# UI_MAIN.net
KiCad netlist of a schematic drawn in Altium Designer
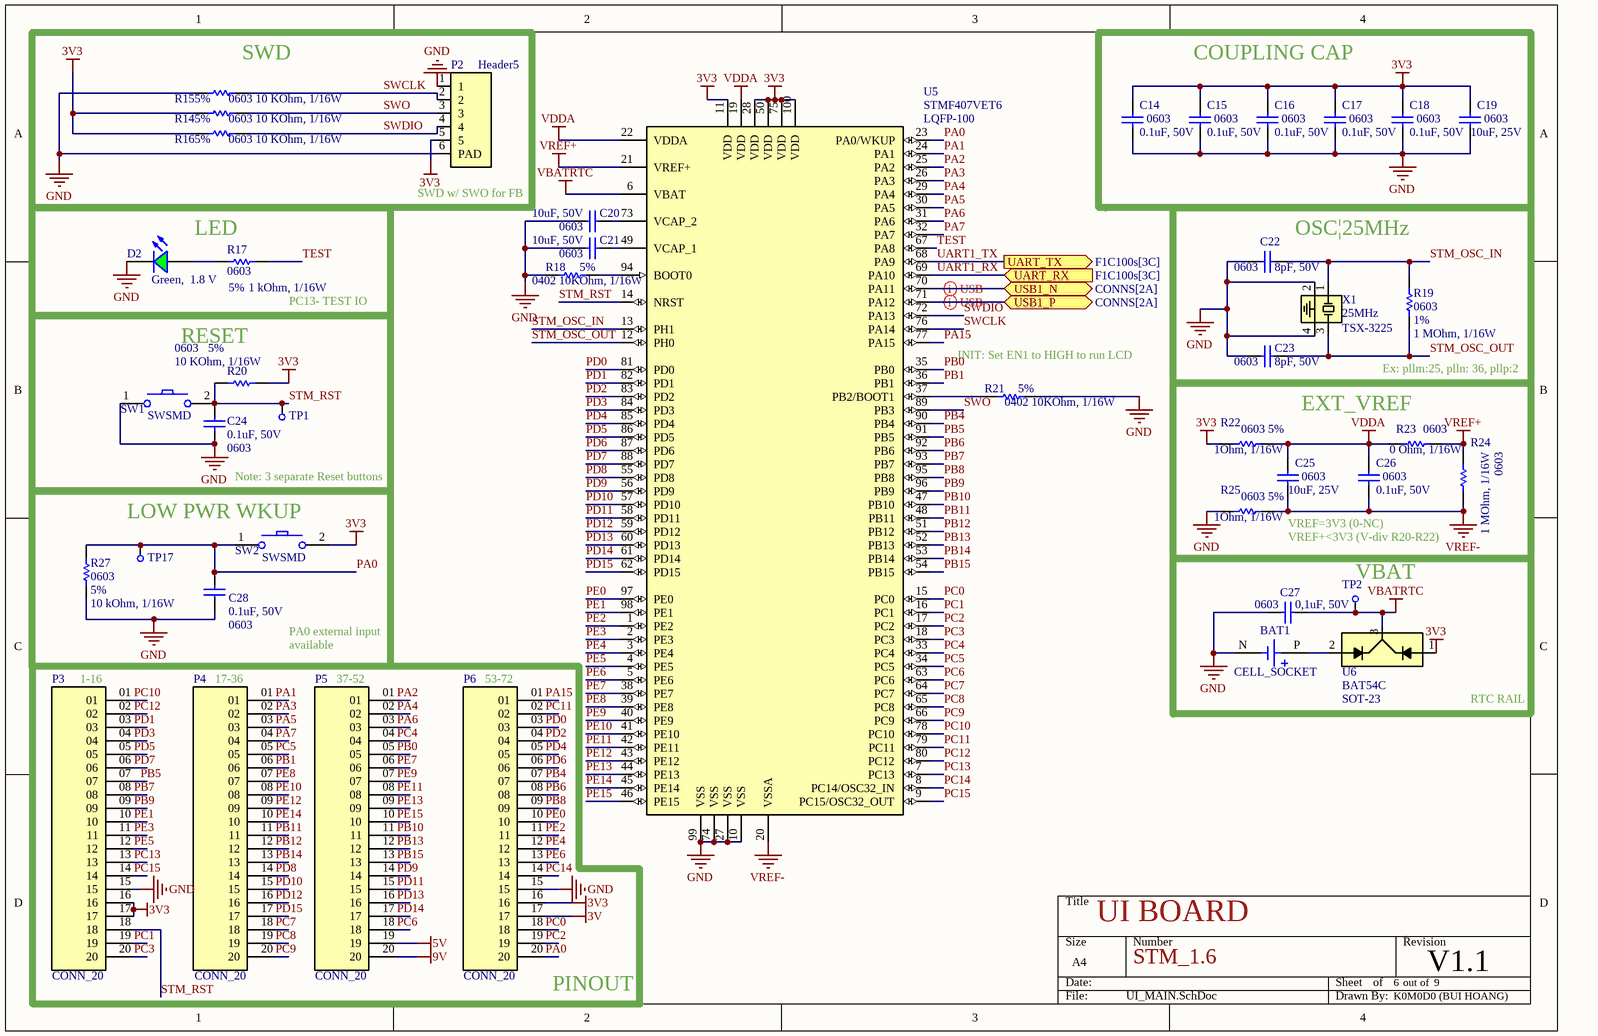
[diagram p0: UI_MAIN.SchDoc]

(export (version "E")
  (design (tool "Eeschema 10.0.6"))
  (components
    (comp (ref "BAT1")
      (value "CELL_SOCKET")
      (footprint "CELL_SOCKET")
      (description "Battery Holder (CELL_PIN)")
      (libsource (lib "DisplayLib") (part "CELL_SOCKET"))
    )
    (comp (ref "C14")
      (value "0.1uF, 50V")
      (footprint "C_0603")
      (description "CAP_0603")
      (fields (field (name "PACKAGE") "0603"))
      (libsource (lib "DisplayLib") (part "CAP_0603"))
    )
    (comp (ref "C15")
      (value "0.1uF, 50V")
      (footprint "C_0603")
      (description "CAP_0603")
      (fields (field (name "PACKAGE") "0603"))
      (libsource (lib "DisplayLib") (part "CAP_0603"))
    )
    (comp (ref "C16")
      (value "0.1uF, 50V")
      (footprint "C_0603")
      (description "CAP_0603")
      (fields (field (name "PACKAGE") "0603"))
      (libsource (lib "DisplayLib") (part "CAP_0603"))
    )
    (comp (ref "C17")
      (value "0.1uF, 50V")
      (footprint "C_0603")
      (description "CAP_0603")
      (fields (field (name "PACKAGE") "0603"))
      (libsource (lib "DisplayLib") (part "CAP_0603"))
    )
    (comp (ref "C18")
      (value "0.1uF, 50V")
      (footprint "C_0603")
      (description "CAP_0603")
      (fields (field (name "PACKAGE") "0603"))
      (libsource (lib "DisplayLib") (part "CAP_0603"))
    )
    (comp (ref "C19")
      (value "10uF, 25V")
      (footprint "C_0603")
      (description "CAP_0603")
      (fields (field (name "PACKAGE") "0603"))
      (libsource (lib "DisplayLib") (part "CAP_0603"))
    )
    (comp (ref "C20")
      (value "10uF, 50V")
      (footprint "C_0603")
      (description "CAP_0603")
      (fields (field (name "PACKAGE") "0603"))
      (libsource (lib "DisplayLib") (part "CAP_0603"))
    )
    (comp (ref "C21")
      (value "10uF, 50V")
      (footprint "C_0603")
      (description "CAP_0603")
      (fields (field (name "PACKAGE") "0603"))
      (libsource (lib "DisplayLib") (part "CAP_0603"))
    )
    (comp (ref "C22")
      (value "8pF, 50V")
      (footprint "C_0603")
      (description "CAP_0603")
      (fields (field (name "PACKAGE") "0603"))
      (libsource (lib "DisplayLib") (part "CAP_0603"))
    )
    (comp (ref "C23")
      (value "8pF, 50V")
      (footprint "C_0603")
      (description "CAP_0603")
      (fields (field (name "PACKAGE") "0603"))
      (libsource (lib "DisplayLib") (part "CAP_0603"))
    )
    (comp (ref "C24")
      (value "0.1uF, 50V")
      (footprint "C_0603")
      (description "CAP_0603")
      (fields (field (name "PACKAGE") "0603"))
      (libsource (lib "DisplayLib") (part "CAP_0603"))
    )
    (comp (ref "C25")
      (value "10uF, 25V")
      (footprint "C_0603")
      (description "CAP_0603")
      (fields (field (name "PACKAGE") "0603"))
      (libsource (lib "DisplayLib") (part "CAP_0603"))
    )
    (comp (ref "C26")
      (value "0.1uF, 50V")
      (footprint "C_0603")
      (description "CAP_0603")
      (fields (field (name "PACKAGE") "0603"))
      (libsource (lib "DisplayLib") (part "CAP_0603"))
    )
    (comp (ref "C27")
      (value "0,1uF, 50V")
      (footprint "C_0603")
      (description "CAP_0603")
      (fields (field (name "PACKAGE") "0603"))
      (libsource (lib "DisplayLib") (part "CAP_0603"))
    )
    (comp (ref "C28")
      (value "0.1uF, 50V")
      (footprint "C_0603")
      (description "CAP_0603")
      (fields (field (name "PACKAGE") "0603"))
      (libsource (lib "DisplayLib") (part "CAP_0603"))
    )
    (comp (ref "D2")
      (value "Green,  1.8 V")
      (footprint "LED_0603")
      (description "Green LED")
      (libsource (lib "DisplayLib") (part "GREEN"))
    )
    (comp (ref "P2")
      (value "Header5")
      (footprint "CONN_Header5")
      (description "Header 5 pins (2.54mm)")
      (libsource (lib "DisplayLib") (part "HEADER5"))
    )
    (comp (ref "P3")
      (value "CONN_20")
      (footprint "CONN_20")
      (description "Header 20 pins (2.54mm)")
      (libsource (lib "DisplayLib") (part "CONN_20"))
    )
    (comp (ref "P4")
      (value "CONN_20")
      (footprint "CONN_20")
      (description "Header 20 pins (2.54mm)")
      (libsource (lib "DisplayLib") (part "CONN_20"))
    )
    (comp (ref "P5")
      (value "CONN_20")
      (footprint "CONN_20")
      (description "Header 20 pins (2.54mm)")
      (libsource (lib "DisplayLib") (part "CONN_20"))
    )
    (comp (ref "P6")
      (value "CONN_20")
      (footprint "CONN_20")
      (description "Header 20 pins (2.54mm)")
      (libsource (lib "DisplayLib") (part "CONN_20"))
    )
    (comp (ref "R14")
      (value "10 KOhm, 1/16W")
      (footprint "R_0603")
      (description "RES_0603")
      (fields (field (name "PACKAGE") "0603") (field (name "ACC") "5%"))
      (libsource (lib "DisplayLib") (part "RES_0603"))
    )
    (comp (ref "R15")
      (value "10 KOhm, 1/16W")
      (footprint "R_0603")
      (description "RES_0603")
      (fields (field (name "PACKAGE") "0603") (field (name "ACC") "5%"))
      (libsource (lib "DisplayLib") (part "RES_0603"))
    )
    (comp (ref "R16")
      (value "10 KOhm, 1/16W")
      (footprint "R_0603")
      (description "RES_0603")
      (fields (field (name "PACKAGE") "0603") (field (name "ACC") "5%"))
      (libsource (lib "DisplayLib") (part "RES_0603"))
    )
    (comp (ref "R17")
      (value "1 kOhm, 1/16W")
      (footprint "R_0603")
      (description "RES_0603")
      (fields (field (name "PACKAGE") "0603") (field (name "ACC") "5%"))
      (libsource (lib "DisplayLib") (part "RES_0603"))
    )
    (comp (ref "R18")
      (value "10KOhm, 1/16W")
      (footprint "R_0402")
      (description "RES_0402")
      (fields (field (name "PACKAGE") "0402") (field (name "ACC") "5%"))
      (libsource (lib "DisplayLib") (part "RES_0402"))
    )
    (comp (ref "R19")
      (value "1 MOhm, 1/16W")
      (footprint "R_0603")
      (description "RES_0603")
      (fields (field (name "PACKAGE") "0603") (field (name "ACC") "1%"))
      (libsource (lib "DisplayLib") (part "RES_0603"))
    )
    (comp (ref "R20")
      (value "10 KOhm, 1/16W")
      (footprint "R_0603")
      (description "RES_0603")
      (fields (field (name "PACKAGE") "0603") (field (name "ACC") "5%"))
      (libsource (lib "DisplayLib") (part "RES_0603"))
    )
    (comp (ref "R21")
      (value "10KOhm, 1/16W")
      (footprint "R_0402")
      (description "RES_0402")
      (fields (field (name "PACKAGE") "0402") (field (name "ACC") "5%"))
      (libsource (lib "DisplayLib") (part "RES_0402"))
    )
    (comp (ref "R22")
      (value "1Ohm, 1/16W")
      (footprint "R_0603")
      (description "RES_0603")
      (fields (field (name "PACKAGE") "0603") (field (name "ACC") "5%"))
      (libsource (lib "DisplayLib") (part "RES_0603"))
    )
    (comp (ref "R23")
      (value "0 Ohm, 1/16W")
      (footprint "R_0603")
      (description "RES_0603")
      (fields (field (name "PACKAGE") "0603"))
      (libsource (lib "DisplayLib") (part "RES_0603"))
    )
    (comp (ref "R24")
      (value "1 MOhm, 1/16W")
      (footprint "R_0603")
      (description "RES_0603")
      (fields (field (name "PACKAGE") "0603"))
      (libsource (lib "DisplayLib") (part "RES_0603"))
    )
    (comp (ref "R25")
      (value "1Ohm, 1/16W")
      (footprint "R_0603")
      (description "RES_0603")
      (fields (field (name "PACKAGE") "0603") (field (name "ACC") "5%"))
      (libsource (lib "DisplayLib") (part "RES_0603"))
    )
    (comp (ref "R27")
      (value "10 kOhm, 1/16W")
      (footprint "R_0603")
      (description "RES_0603")
      (fields (field (name "PACKAGE") "0603") (field (name "ACC") "5%"))
      (libsource (lib "DisplayLib") (part "RES_0603"))
    )
    (comp (ref "SW1")
      (value "SWSMD")
      (footprint "SW_SMD_NOGND")
      (description "SW_SMD")
      (libsource (lib "DisplayLib") (part "SWSMD_NOGND"))
    )
    (comp (ref "SW2")
      (value "SWSMD")
      (footprint "SW_SMD_NOGND")
      (description "SW_SMD")
      (libsource (lib "DisplayLib") (part "SWSMD_NOGND"))
    )
    (comp (ref "TP1")
      (value "TESTPT")
      (footprint "TESTPT")
      (description "Test point")
      (libsource (lib "DisplayLib") (part "TESTPT"))
    )
    (comp (ref "TP2")
      (value "TESTPT")
      (footprint "TESTPT")
      (description "Test point")
      (libsource (lib "DisplayLib") (part "TESTPT"))
    )
    (comp (ref "TP17")
      (value "TESTPT")
      (footprint "TESTPT")
      (description "Test point")
      (libsource (lib "DisplayLib") (part "TESTPT"))
    )
    (comp (ref "U5")
      (value "STMF407VET6")
      (footprint "PKG_LQFP-100")
      (fields (field (name "PACKAGE") "LQFP-100"))
      (libsource (lib "DisplayLib") (part "STMF407VET6"))
    )
    (comp (ref "U6")
      (value "BAT54C")
      (footprint "PKG_SOT-23")
      (description "P-Channel 30 V 4A (Ta) 1.4W (Ta) Surface Mount SOT-23-3")
      (fields (field (name "PACKAGE") "SOT-23"))
      (libsource (lib "DisplayLib") (part "BAT54C"))
    )
    (comp (ref "X1")
      (value "25MHz")
      (footprint "PKG_TSX-3225")
      (description "Crystal, 25 MHz, -30 to 85 degC, 3.2 x 2.5 x 0.9 mm SMD")
      (fields (field (name "PACKAGE") "TSX-3225"))
      (libsource (lib "DisplayLib") (part "XTAL"))
    )
  )
  (nets
    (net (code "1") (name "/PA0") (class "Default")
      (node (ref "C28") (pin "2") (pinfunction "2_2") (pintype "passive"))
      (node (ref "P6") (pin "20") (pinfunction "20_20") (pintype "passive"))
      (node (ref "R27") (pin "2") (pinfunction "2_2") (pintype "passive"))
      (node (ref "SW2") (pin "1") (pinfunction "1_1") (pintype "passive"))
      (node (ref "TP17") (pin "1") (pinfunction "1_1") (pintype "passive"))
      (node (ref "U5") (pin "23") (pinfunction "PA0/WKUP_23") (pintype "bidirectional"))
    )
    (net (code "2") (name "/PA1") (class "Default")
      (node (ref "P4") (pin "01") (pinfunction "01_01") (pintype "passive"))
      (node (ref "U5") (pin "24") (pinfunction "PA1_24") (pintype "bidirectional"))
    )
    (net (code "3") (name "/PA2") (class "Default")
      (node (ref "P5") (pin "01") (pinfunction "01_01") (pintype "passive"))
      (node (ref "U5") (pin "25") (pinfunction "PA2_25") (pintype "bidirectional"))
    )
    (net (code "4") (name "/PA3") (class "Default")
      (node (ref "P4") (pin "02") (pinfunction "02_02") (pintype "passive"))
      (node (ref "U5") (pin "26") (pinfunction "PA3_26") (pintype "bidirectional"))
    )
    (net (code "5") (name "/PA4") (class "Default")
      (node (ref "P5") (pin "02") (pinfunction "02_02") (pintype "passive"))
      (node (ref "U5") (pin "29") (pinfunction "PA4_29") (pintype "bidirectional"))
    )
    (net (code "6") (name "/PA5") (class "Default")
      (node (ref "P4") (pin "03") (pinfunction "03_03") (pintype "passive"))
      (node (ref "U5") (pin "30") (pinfunction "PA5_30") (pintype "bidirectional"))
    )
    (net (code "7") (name "/PA6") (class "Default")
      (node (ref "P5") (pin "03") (pinfunction "03_03") (pintype "passive"))
      (node (ref "U5") (pin "31") (pinfunction "PA6_31") (pintype "bidirectional"))
    )
    (net (code "8") (name "/PA7") (class "Default")
      (node (ref "P4") (pin "04") (pinfunction "04_04") (pintype "passive"))
      (node (ref "U5") (pin "32") (pinfunction "PA7_32") (pintype "bidirectional"))
    )
    (net (code "9") (name "/PA15") (class "Default")
      (node (ref "P6") (pin "01") (pinfunction "01_01") (pintype "passive"))
      (node (ref "U5") (pin "77") (pinfunction "PA15_77") (pintype "bidirectional"))
    )
    (net (code "10") (name "/PB0") (class "Default")
      (node (ref "P5") (pin "05") (pinfunction "05_05") (pintype "passive"))
      (node (ref "U5") (pin "35") (pinfunction "PB0_35") (pintype "bidirectional"))
    )
    (net (code "11") (name "/PB1") (class "Default")
      (node (ref "P4") (pin "06") (pinfunction "06_06") (pintype "passive"))
      (node (ref "U5") (pin "36") (pinfunction "PB1_36") (pintype "bidirectional"))
    )
    (net (code "12") (name "/PB4") (class "Default")
      (node (ref "P6") (pin "07") (pinfunction "07_07") (pintype "passive"))
      (node (ref "U5") (pin "90") (pinfunction "PB4_90") (pintype "bidirectional"))
    )
    (net (code "13") (name "/PB5") (class "Default")
      (node (ref "P3") (pin "07") (pinfunction "07_07") (pintype "passive"))
      (node (ref "U5") (pin "91") (pinfunction "PB5_91") (pintype "bidirectional"))
    )
    (net (code "14") (name "/PB6") (class "Default")
      (node (ref "P6") (pin "08") (pinfunction "08_08") (pintype "passive"))
      (node (ref "U5") (pin "92") (pinfunction "PB6_92") (pintype "bidirectional"))
    )
    (net (code "15") (name "/PB7") (class "Default")
      (node (ref "P3") (pin "08") (pinfunction "08_08") (pintype "passive"))
      (node (ref "U5") (pin "93") (pinfunction "PB7_93") (pintype "bidirectional"))
    )
    (net (code "16") (name "/PB8") (class "Default")
      (node (ref "P6") (pin "09") (pinfunction "09_09") (pintype "passive"))
      (node (ref "U5") (pin "95") (pinfunction "PB8_95") (pintype "bidirectional"))
    )
    (net (code "17") (name "/PB9") (class "Default")
      (node (ref "P3") (pin "09") (pinfunction "09_09") (pintype "passive"))
      (node (ref "U5") (pin "96") (pinfunction "PB9_96") (pintype "bidirectional"))
    )
    (net (code "18") (name "/PB10") (class "Default")
      (node (ref "P5") (pin "11") (pinfunction "11_11") (pintype "passive"))
      (node (ref "U5") (pin "47") (pinfunction "PB10_47") (pintype "bidirectional"))
    )
    (net (code "19") (name "/PB11") (class "Default")
      (node (ref "P4") (pin "11") (pinfunction "11_11") (pintype "passive"))
      (node (ref "U5") (pin "48") (pinfunction "PB11_48") (pintype "bidirectional"))
    )
    (net (code "20") (name "/PB12") (class "Default")
      (node (ref "P4") (pin "12") (pinfunction "12_12") (pintype "passive"))
      (node (ref "U5") (pin "51") (pinfunction "PB12_51") (pintype "bidirectional"))
    )
    (net (code "21") (name "/PB13") (class "Default")
      (node (ref "P5") (pin "12") (pinfunction "12_12") (pintype "passive"))
      (node (ref "U5") (pin "52") (pinfunction "PB13_52") (pintype "bidirectional"))
    )
    (net (code "22") (name "/PB14") (class "Default")
      (node (ref "P4") (pin "13") (pinfunction "13_13") (pintype "passive"))
      (node (ref "U5") (pin "53") (pinfunction "PB14_53") (pintype "bidirectional"))
    )
    (net (code "23") (name "/PB15") (class "Default")
      (node (ref "P5") (pin "13") (pinfunction "13_13") (pintype "passive"))
      (node (ref "U5") (pin "54") (pinfunction "PB15_54") (pintype "bidirectional"))
    )
    (net (code "24") (name "/PC0") (class "Default")
      (node (ref "P6") (pin "18") (pinfunction "18_18") (pintype "passive"))
      (node (ref "U5") (pin "15") (pinfunction "PC0_15") (pintype "bidirectional"))
    )
    (net (code "25") (name "/PC1") (class "Default")
      (node (ref "P3") (pin "19") (pinfunction "19_19") (pintype "passive"))
      (node (ref "U5") (pin "16") (pinfunction "PC1_16") (pintype "bidirectional"))
    )
    (net (code "26") (name "/PC2") (class "Default")
      (node (ref "P6") (pin "19") (pinfunction "19_19") (pintype "passive"))
      (node (ref "U5") (pin "17") (pinfunction "PC2_17") (pintype "bidirectional"))
    )
    (net (code "27") (name "/PC3") (class "Default")
      (node (ref "P3") (pin "20") (pinfunction "20_20") (pintype "passive"))
      (node (ref "U5") (pin "18") (pinfunction "PC3_18") (pintype "bidirectional"))
    )
    (net (code "28") (name "/PC4") (class "Default")
      (node (ref "P5") (pin "04") (pinfunction "04_04") (pintype "passive"))
      (node (ref "U5") (pin "33") (pinfunction "PC4_33") (pintype "bidirectional"))
    )
    (net (code "29") (name "/PC5") (class "Default")
      (node (ref "P4") (pin "05") (pinfunction "05_05") (pintype "passive"))
      (node (ref "U5") (pin "34") (pinfunction "PC5_34") (pintype "bidirectional"))
    )
    (net (code "30") (name "/PC6") (class "Default")
      (node (ref "P5") (pin "18") (pinfunction "18_18") (pintype "passive"))
      (node (ref "U5") (pin "63") (pinfunction "PC6_63") (pintype "bidirectional"))
    )
    (net (code "31") (name "/PC7") (class "Default")
      (node (ref "P4") (pin "18") (pinfunction "18_18") (pintype "passive"))
      (node (ref "U5") (pin "64") (pinfunction "PC7_64") (pintype "bidirectional"))
    )
    (net (code "32") (name "/PC8") (class "Default")
      (node (ref "P4") (pin "19") (pinfunction "19_19") (pintype "passive"))
      (node (ref "U5") (pin "65") (pinfunction "PC8_65") (pintype "bidirectional"))
    )
    (net (code "33") (name "/PC9") (class "Default")
      (node (ref "P4") (pin "20") (pinfunction "20_20") (pintype "passive"))
      (node (ref "U5") (pin "66") (pinfunction "PC9_66") (pintype "bidirectional"))
    )
    (net (code "34") (name "/PC10") (class "Default")
      (node (ref "P3") (pin "01") (pinfunction "01_01") (pintype "passive"))
      (node (ref "U5") (pin "78") (pinfunction "PC10_78") (pintype "bidirectional"))
    )
    (net (code "35") (name "/PC11") (class "Default")
      (node (ref "P6") (pin "02") (pinfunction "02_02") (pintype "passive"))
      (node (ref "U5") (pin "79") (pinfunction "PC11_79") (pintype "bidirectional"))
    )
    (net (code "36") (name "/PC12") (class "Default")
      (node (ref "P3") (pin "02") (pinfunction "02_02") (pintype "passive"))
      (node (ref "U5") (pin "80") (pinfunction "PC12_80") (pintype "bidirectional"))
    )
    (net (code "37") (name "/PC13") (class "Default")
      (node (ref "P3") (pin "13") (pinfunction "13_13") (pintype "passive"))
      (node (ref "U5") (pin "7") (pinfunction "PC13_7") (pintype "bidirectional"))
    )
    (net (code "38") (name "/PC14") (class "Default")
      (node (ref "P6") (pin "14") (pinfunction "14_14") (pintype "passive"))
      (node (ref "U5") (pin "8") (pinfunction "PC14/OSC32_IN_8") (pintype "bidirectional"))
    )
    (net (code "39") (name "/PC15") (class "Default")
      (node (ref "P3") (pin "14") (pinfunction "14_14") (pintype "passive"))
      (node (ref "U5") (pin "9") (pinfunction "PC15/OSC32_OUT_9") (pintype "bidirectional"))
    )
    (net (code "40") (name "/PD0") (class "Default")
      (node (ref "P6") (pin "03") (pinfunction "03_03") (pintype "passive"))
      (node (ref "U5") (pin "81") (pinfunction "PD0_81") (pintype "bidirectional"))
    )
    (net (code "41") (name "/PD1") (class "Default")
      (node (ref "P3") (pin "03") (pinfunction "03_03") (pintype "passive"))
      (node (ref "U5") (pin "82") (pinfunction "PD1_82") (pintype "bidirectional"))
    )
    (net (code "42") (name "/PD2") (class "Default")
      (node (ref "P6") (pin "04") (pinfunction "04_04") (pintype "passive"))
      (node (ref "U5") (pin "83") (pinfunction "PD2_83") (pintype "bidirectional"))
    )
    (net (code "43") (name "/PD3") (class "Default")
      (node (ref "P3") (pin "04") (pinfunction "04_04") (pintype "passive"))
      (node (ref "U5") (pin "84") (pinfunction "PD3_84") (pintype "bidirectional"))
    )
    (net (code "44") (name "/PD4") (class "Default")
      (node (ref "P6") (pin "05") (pinfunction "05_05") (pintype "passive"))
      (node (ref "U5") (pin "85") (pinfunction "PD4_85") (pintype "bidirectional"))
    )
    (net (code "45") (name "/PD5") (class "Default")
      (node (ref "P3") (pin "05") (pinfunction "05_05") (pintype "passive"))
      (node (ref "U5") (pin "86") (pinfunction "PD5_86") (pintype "bidirectional"))
    )
    (net (code "46") (name "/PD6") (class "Default")
      (node (ref "P6") (pin "06") (pinfunction "06_06") (pintype "passive"))
      (node (ref "U5") (pin "87") (pinfunction "PD6_87") (pintype "bidirectional"))
    )
    (net (code "47") (name "/PD7") (class "Default")
      (node (ref "P3") (pin "06") (pinfunction "06_06") (pintype "passive"))
      (node (ref "U5") (pin "88") (pinfunction "PD7_88") (pintype "bidirectional"))
    )
    (net (code "48") (name "/PD8") (class "Default")
      (node (ref "P4") (pin "14") (pinfunction "14_14") (pintype "passive"))
      (node (ref "U5") (pin "55") (pinfunction "PD8_55") (pintype "bidirectional"))
    )
    (net (code "49") (name "/PD9") (class "Default")
      (node (ref "P5") (pin "14") (pinfunction "14_14") (pintype "passive"))
      (node (ref "U5") (pin "56") (pinfunction "PD9_56") (pintype "bidirectional"))
    )
    (net (code "50") (name "/PD10") (class "Default")
      (node (ref "P4") (pin "15") (pinfunction "15_15") (pintype "passive"))
      (node (ref "U5") (pin "57") (pinfunction "PD10_57") (pintype "bidirectional"))
    )
    (net (code "51") (name "/PD11") (class "Default")
      (node (ref "P5") (pin "15") (pinfunction "15_15") (pintype "passive"))
      (node (ref "U5") (pin "58") (pinfunction "PD11_58") (pintype "bidirectional"))
    )
    (net (code "52") (name "/PD12") (class "Default")
      (node (ref "P4") (pin "16") (pinfunction "16_16") (pintype "passive"))
      (node (ref "U5") (pin "59") (pinfunction "PD12_59") (pintype "bidirectional"))
    )
    (net (code "53") (name "/PD13") (class "Default")
      (node (ref "P5") (pin "16") (pinfunction "16_16") (pintype "passive"))
      (node (ref "U5") (pin "60") (pinfunction "PD13_60") (pintype "bidirectional"))
    )
    (net (code "54") (name "/PD14") (class "Default")
      (node (ref "P5") (pin "17") (pinfunction "17_17") (pintype "passive"))
      (node (ref "U5") (pin "61") (pinfunction "PD14_61") (pintype "bidirectional"))
    )
    (net (code "55") (name "/PD15") (class "Default")
      (node (ref "P4") (pin "17") (pinfunction "17_17") (pintype "passive"))
      (node (ref "U5") (pin "62") (pinfunction "PD15_62") (pintype "bidirectional"))
    )
    (net (code "56") (name "/PE0") (class "Default")
      (node (ref "P6") (pin "10") (pinfunction "10_10") (pintype "passive"))
      (node (ref "U5") (pin "97") (pinfunction "PE0_97") (pintype "bidirectional"))
    )
    (net (code "57") (name "/PE1") (class "Default")
      (node (ref "P3") (pin "10") (pinfunction "10_10") (pintype "passive"))
      (node (ref "U5") (pin "98") (pinfunction "PE1_98") (pintype "bidirectional"))
    )
    (net (code "58") (name "/PE2") (class "Default")
      (node (ref "P6") (pin "11") (pinfunction "11_11") (pintype "passive"))
      (node (ref "U5") (pin "1") (pinfunction "PE2_1") (pintype "bidirectional"))
    )
    (net (code "59") (name "/PE3") (class "Default")
      (node (ref "P3") (pin "11") (pinfunction "11_11") (pintype "passive"))
      (node (ref "U5") (pin "2") (pinfunction "PE3_2") (pintype "bidirectional"))
    )
    (net (code "60") (name "/PE4") (class "Default")
      (node (ref "P6") (pin "12") (pinfunction "12_12") (pintype "passive"))
      (node (ref "U5") (pin "3") (pinfunction "PE4_3") (pintype "bidirectional"))
    )
    (net (code "61") (name "/PE5") (class "Default")
      (node (ref "P3") (pin "12") (pinfunction "12_12") (pintype "passive"))
      (node (ref "U5") (pin "4") (pinfunction "PE5_4") (pintype "bidirectional"))
    )
    (net (code "62") (name "/PE6") (class "Default")
      (node (ref "P6") (pin "13") (pinfunction "13_13") (pintype "passive"))
      (node (ref "U5") (pin "5") (pinfunction "PE6_5") (pintype "bidirectional"))
    )
    (net (code "63") (name "/PE7") (class "Default")
      (node (ref "P5") (pin "06") (pinfunction "06_06") (pintype "passive"))
      (node (ref "U5") (pin "38") (pinfunction "PE7_38") (pintype "bidirectional"))
    )
    (net (code "64") (name "/PE8") (class "Default")
      (node (ref "P4") (pin "07") (pinfunction "07_07") (pintype "passive"))
      (node (ref "U5") (pin "39") (pinfunction "PE8_39") (pintype "bidirectional"))
    )
    (net (code "65") (name "/PE9") (class "Default")
      (node (ref "P5") (pin "07") (pinfunction "07_07") (pintype "passive"))
      (node (ref "U5") (pin "40") (pinfunction "PE9_40") (pintype "bidirectional"))
    )
    (net (code "66") (name "/PE10") (class "Default")
      (node (ref "P4") (pin "08") (pinfunction "08_08") (pintype "passive"))
      (node (ref "U5") (pin "41") (pinfunction "PE10_41") (pintype "bidirectional"))
    )
    (net (code "67") (name "/PE11") (class "Default")
      (node (ref "P5") (pin "08") (pinfunction "08_08") (pintype "passive"))
      (node (ref "U5") (pin "42") (pinfunction "PE11_42") (pintype "bidirectional"))
    )
    (net (code "68") (name "/PE12") (class "Default")
      (node (ref "P4") (pin "09") (pinfunction "09_09") (pintype "passive"))
      (node (ref "U5") (pin "43") (pinfunction "PE12_43") (pintype "bidirectional"))
    )
    (net (code "69") (name "/PE13") (class "Default")
      (node (ref "P5") (pin "09") (pinfunction "09_09") (pintype "passive"))
      (node (ref "U5") (pin "44") (pinfunction "PE13_44") (pintype "bidirectional"))
    )
    (net (code "70") (name "/PE14") (class "Default")
      (node (ref "P4") (pin "10") (pinfunction "10_10") (pintype "passive"))
      (node (ref "U5") (pin "45") (pinfunction "PE14_45") (pintype "bidirectional"))
    )
    (net (code "71") (name "/PE15") (class "Default")
      (node (ref "P5") (pin "10") (pinfunction "10_10") (pintype "passive"))
      (node (ref "U5") (pin "46") (pinfunction "PE15_46") (pintype "bidirectional"))
    )
    (net (code "72") (name "/STM_OSC_IN") (class "Default")
      (node (ref "C22") (pin "2") (pinfunction "2_2") (pintype "passive"))
      (node (ref "R19") (pin "2") (pinfunction "2_2") (pintype "passive"))
      (node (ref "U5") (pin "13") (pinfunction "PH1_13") (pintype "bidirectional"))
      (node (ref "X1") (pin "1") (pinfunction "1_1") (pintype "passive"))
    )
    (net (code "73") (name "/STM_OSC_OUT") (class "Default")
      (node (ref "C23") (pin "2") (pinfunction "2_2") (pintype "passive"))
      (node (ref "R19") (pin "1") (pinfunction "1_1") (pintype "passive"))
      (node (ref "U5") (pin "12") (pinfunction "PH0_12") (pintype "bidirectional"))
      (node (ref "X1") (pin "3") (pinfunction "3_3") (pintype "passive"))
    )
    (net (code "74") (name "/STM_RST") (class "Default")
      (node (ref "C24") (pin "2") (pinfunction "2_2") (pintype "passive"))
      (node (ref "P3") (pin "18") (pinfunction "18_18") (pintype "passive"))
      (node (ref "R20") (pin "1") (pinfunction "1_1") (pintype "passive"))
      (node (ref "SW1") (pin "2") (pinfunction "2_2") (pintype "passive"))
      (node (ref "TP1") (pin "1") (pinfunction "1_1") (pintype "passive"))
      (node (ref "U5") (pin "14") (pinfunction "NRST_14") (pintype "bidirectional"))
    )
    (net (code "75") (name "/SWCLK") (class "Default")
      (node (ref "P2") (pin "2") (pinfunction "2_2") (pintype "passive"))
      (node (ref "R15") (pin "2") (pinfunction "2_2") (pintype "passive"))
      (node (ref "U5") (pin "76") (pinfunction "PA14_76") (pintype "bidirectional"))
    )
    (net (code "76") (name "/SWDIO") (class "Default")
      (node (ref "P2") (pin "4") (pinfunction "4_4") (pintype "passive"))
      (node (ref "R16") (pin "2") (pinfunction "2_2") (pintype "passive"))
      (node (ref "U5") (pin "72") (pinfunction "PA13_72") (pintype "bidirectional"))
    )
    (net (code "77") (name "/SWO") (class "Default")
      (node (ref "P2") (pin "3") (pinfunction "3_3") (pintype "passive"))
      (node (ref "R14") (pin "2") (pinfunction "2_2") (pintype "passive"))
      (node (ref "U5") (pin "89") (pinfunction "PB3_89") (pintype "bidirectional"))
    )
    (net (code "78") (name "/TEST") (class "Default")
      (node (ref "R17") (pin "2") (pinfunction "2_2") (pintype "passive"))
      (node (ref "U5") (pin "67") (pinfunction "PA8_67") (pintype "bidirectional"))
    )
    (net (code "79") (name "/UART1_RX") (class "Default")
      (node (ref "U5") (pin "69") (pinfunction "PA10_69") (pintype "bidirectional"))
    )
    (net (code "80") (name "/UART1_TX") (class "Default")
      (node (ref "U5") (pin "68") (pinfunction "PA9_68") (pintype "bidirectional"))
    )
    (net (code "81") (name "/USB1_N") (class "Default")
      (node (ref "U5") (pin "70") (pinfunction "PA11_70") (pintype "bidirectional"))
    )
    (net (code "82") (name "/USB1_P") (class "Default")
      (node (ref "U5") (pin "71") (pinfunction "PA12_71") (pintype "bidirectional"))
    )
    (net (code "83") (name "3V") (class "Default")
      (node (ref "P6") (pin "17") (pinfunction "17_17") (pintype "passive"))
    )
    (net (code "84") (name "3V3") (class "Default")
      (node (ref "C14") (pin "2") (pinfunction "2_2") (pintype "passive"))
      (node (ref "C15") (pin "2") (pinfunction "2_2") (pintype "passive"))
      (node (ref "C16") (pin "2") (pinfunction "2_2") (pintype "passive"))
      (node (ref "C17") (pin "2") (pinfunction "2_2") (pintype "passive"))
      (node (ref "C18") (pin "2") (pinfunction "2_2") (pintype "passive"))
      (node (ref "C19") (pin "2") (pinfunction "2_2") (pintype "passive"))
      (node (ref "P2") (pin "5") (pinfunction "5_5") (pintype "passive"))
      (node (ref "P3") (pin "16") (pinfunction "16_16") (pintype "passive"))
      (node (ref "P3") (pin "17") (pinfunction "17_17") (pintype "passive"))
      (node (ref "P6") (pin "16") (pinfunction "16_16") (pintype "passive"))
      (node (ref "R14") (pin "1") (pinfunction "1_1") (pintype "passive"))
      (node (ref "R16") (pin "1") (pinfunction "1_1") (pintype "passive"))
      (node (ref "R20") (pin "2") (pinfunction "2_2") (pintype "passive"))
      (node (ref "R22") (pin "1") (pinfunction "1_1") (pintype "passive"))
      (node (ref "SW2") (pin "2") (pinfunction "2_2") (pintype "passive"))
      (node (ref "U5") (pin "100") (pinfunction "VDD_100") (pintype "power_in"))
      (node (ref "U5") (pin "11") (pinfunction "VDD_11") (pintype "power_in"))
      (node (ref "U5") (pin "28") (pinfunction "VDD_28") (pintype "power_in"))
      (node (ref "U5") (pin "50") (pinfunction "VDD_50") (pintype "power_in"))
      (node (ref "U5") (pin "75") (pinfunction "VDD_75") (pintype "power_in"))
      (node (ref "U6") (pin "1") (pinfunction "1_1") (pintype "power_in"))
    )
    (net (code "85") (name "5V") (class "Default")
      (node (ref "P5") (pin "19") (pinfunction "19_19") (pintype "passive"))
    )
    (net (code "86") (name "9V") (class "Default")
      (node (ref "P5") (pin "20") (pinfunction "20_20") (pintype "passive"))
    )
    (net (code "87") (name "GND") (class "Default")
      (node (ref "BAT1") (pin "N") (pinfunction "N_N") (pintype "passive"))
      (node (ref "C14") (pin "1") (pinfunction "1_1") (pintype "passive"))
      (node (ref "C15") (pin "1") (pinfunction "1_1") (pintype "passive"))
      (node (ref "C16") (pin "1") (pinfunction "1_1") (pintype "passive"))
      (node (ref "C17") (pin "1") (pinfunction "1_1") (pintype "passive"))
      (node (ref "C18") (pin "1") (pinfunction "1_1") (pintype "passive"))
      (node (ref "C19") (pin "1") (pinfunction "1_1") (pintype "passive"))
      (node (ref "C20") (pin "2") (pinfunction "2_2") (pintype "passive"))
      (node (ref "C21") (pin "2") (pinfunction "2_2") (pintype "passive"))
      (node (ref "C22") (pin "1") (pinfunction "1_1") (pintype "passive"))
      (node (ref "C23") (pin "1") (pinfunction "1_1") (pintype "passive"))
      (node (ref "C24") (pin "1") (pinfunction "1_1") (pintype "passive"))
      (node (ref "C27") (pin "1") (pinfunction "1_1") (pintype "passive"))
      (node (ref "C28") (pin "1") (pinfunction "1_1") (pintype "passive"))
      (node (ref "D2") (pin "1") (pinfunction "K_1") (pintype "passive"))
      (node (ref "P2") (pin "1") (pinfunction "1_1") (pintype "passive"))
      (node (ref "P2") (pin "6") (pinfunction "PAD_6") (pintype "passive"))
      (node (ref "P3") (pin "15") (pinfunction "15_15") (pintype "passive"))
      (node (ref "P6") (pin "15") (pinfunction "15_15") (pintype "passive"))
      (node (ref "R15") (pin "1") (pinfunction "1_1") (pintype "passive"))
      (node (ref "R18") (pin "1") (pinfunction "1_1") (pintype "passive"))
      (node (ref "R21") (pin "2") (pinfunction "2_2") (pintype "passive"))
      (node (ref "R25") (pin "1") (pinfunction "1_1") (pintype "passive"))
      (node (ref "R27") (pin "1") (pinfunction "1_1") (pintype "passive"))
      (node (ref "SW1") (pin "1") (pinfunction "1_1") (pintype "passive"))
      (node (ref "U5") (pin "10") (pinfunction "VSS_10") (pintype "power_in"))
      (node (ref "U5") (pin "27") (pinfunction "VSS_27") (pintype "power_in"))
      (node (ref "U5") (pin "74") (pinfunction "VSS_74") (pintype "power_in"))
      (node (ref "U5") (pin "99") (pinfunction "VSS_99") (pintype "power_in"))
      (node (ref "X1") (pin "2") (pinfunction "2_2") (pintype "passive"))
      (node (ref "X1") (pin "4") (pinfunction "4_4") (pintype "passive"))
    )
    (net (code "88") (name "Net-(BAT1-PadP)") (class "Default")
      (node (ref "BAT1") (pin "P") (pinfunction "P_P") (pintype "passive"))
      (node (ref "U6") (pin "2") (pinfunction "2_2") (pintype "passive"))
    )
    (net (code "89") (name "Net-(D2-A)") (class "Default")
      (node (ref "D2") (pin "2") (pinfunction "A_2") (pintype "passive"))
      (node (ref "R17") (pin "1") (pinfunction "1_1") (pintype "passive"))
    )
    (net (code "90") (name "Net-(U5-BOOT0)") (class "Default")
      (node (ref "R18") (pin "2") (pinfunction "2_2") (pintype "passive"))
      (node (ref "U5") (pin "94") (pinfunction "BOOT0_94") (pintype "input"))
    )
    (net (code "91") (name "Net-(U5-PB2{slash}BOOT1)") (class "Default")
      (node (ref "R21") (pin "1") (pinfunction "1_1") (pintype "passive"))
      (node (ref "U5") (pin "37") (pinfunction "PB2/BOOT1_37") (pintype "bidirectional"))
    )
    (net (code "92") (name "Net-(U5-VCAP_1)") (class "Default")
      (node (ref "C21") (pin "1") (pinfunction "1_1") (pintype "passive"))
      (node (ref "U5") (pin "49") (pinfunction "VCAP_1_49") (pintype "power_in"))
    )
    (net (code "93") (name "Net-(U5-VCAP_2)") (class "Default")
      (node (ref "C20") (pin "1") (pinfunction "1_1") (pintype "passive"))
      (node (ref "U5") (pin "73") (pinfunction "VCAP_2_73") (pintype "power_in"))
    )
    (net (code "94") (name "VBATRTC") (class "Default")
      (node (ref "C27") (pin "2") (pinfunction "2_2") (pintype "passive"))
      (node (ref "TP2") (pin "1") (pinfunction "1_1") (pintype "passive"))
      (node (ref "U5") (pin "6") (pinfunction "VBAT_6") (pintype "power_in"))
      (node (ref "U6") (pin "3") (pinfunction "3_3") (pintype "passive"))
    )
    (net (code "95") (name "VDDA") (class "Default")
      (node (ref "C25") (pin "2") (pinfunction "2_2") (pintype "passive"))
      (node (ref "C26") (pin "2") (pinfunction "2_2") (pintype "passive"))
      (node (ref "R22") (pin "2") (pinfunction "2_2") (pintype "passive"))
      (node (ref "R23") (pin "1") (pinfunction "1_1") (pintype "passive"))
      (node (ref "U5") (pin "19") (pinfunction "VDD_19") (pintype "power_in"))
      (node (ref "U5") (pin "22") (pinfunction "VDDA_22") (pintype "power_in"))
    )
    (net (code "96") (name "VREF+") (class "Default")
      (node (ref "R23") (pin "2") (pinfunction "2_2") (pintype "passive"))
      (node (ref "R24") (pin "2") (pinfunction "2_2") (pintype "passive"))
      (node (ref "U5") (pin "21") (pinfunction "VREF+_21") (pintype "power_in"))
    )
    (net (code "97") (name "VREF-") (class "Default")
      (node (ref "C25") (pin "1") (pinfunction "1_1") (pintype "passive"))
      (node (ref "C26") (pin "1") (pinfunction "1_1") (pintype "passive"))
      (node (ref "R24") (pin "1") (pinfunction "1_1") (pintype "passive"))
      (node (ref "R25") (pin "2") (pinfunction "2_2") (pintype "passive"))
      (node (ref "U5") (pin "20") (pinfunction "VSSA_20") (pintype "power_in"))
    )
  )
)
